# Power_Supply.net
KiCad netlist of a schematic drawn in Altium Designer
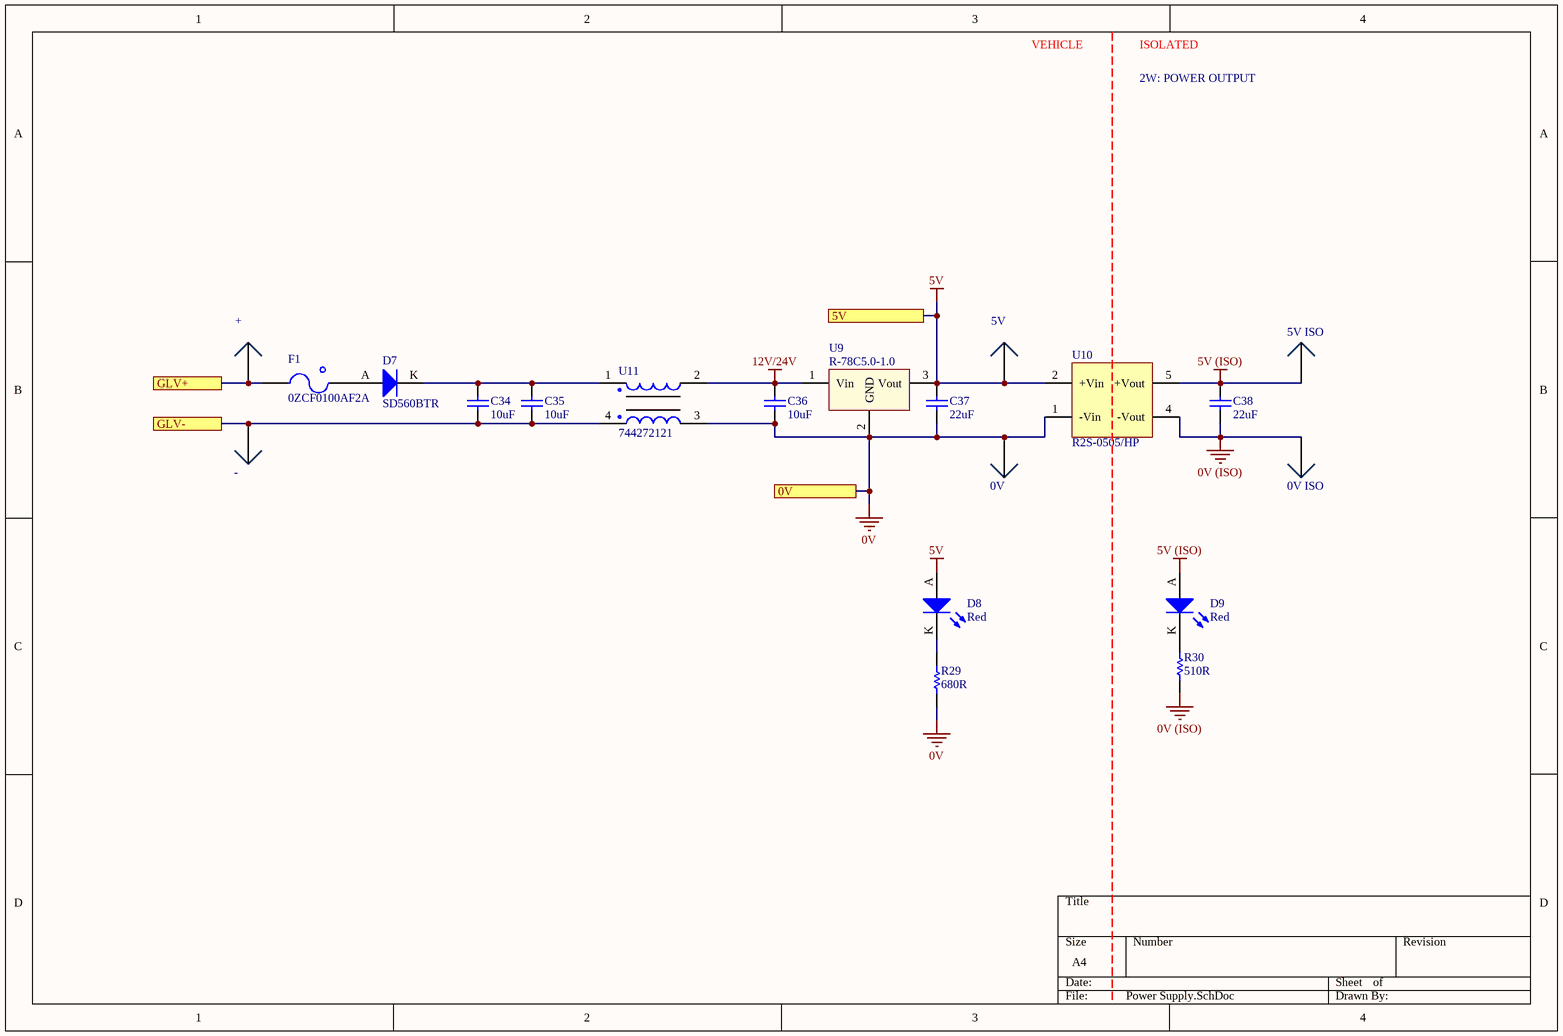
[diagram p0: Power Supply.SchDoc]

(export (version "E")
  (design (tool "Eeschema 10.0.6"))
  (components
    (comp (ref "+")
      (value "0mm")
      (footprint "SMD Test Point")
      (fields (field (name "PART NUMBER") "SMD Test Point") (field (name "CONTACT") "NA"))
      (libsource (lib "ts_20-standard-connectors") (part "Test Point"))
    )
    (comp (ref "-")
      (value "0mm")
      (footprint "SMD Test Point")
      (fields (field (name "PART NUMBER") "SMD Test Point") (field (name "CONTACT") "NA"))
      (libsource (lib "ts_20-standard-connectors") (part "Test Point"))
    )
    (comp (ref "0V")
      (value "0mm")
      (footprint "SMD Test Point")
      (fields (field (name "PART NUMBER") "SMD Test Point") (field (name "CONTACT") "NA"))
      (libsource (lib "ts_20-standard-connectors") (part "Test Point"))
    )
    (comp (ref "0V ISO")
      (value "0mm")
      (footprint "SMD Test Point")
      (fields (field (name "PART NUMBER") "SMD Test Point") (field (name "CONTACT") "NA"))
      (libsource (lib "ts_20-standard-connectors") (part "Test Point"))
    )
    (comp (ref "5V")
      (value "0mm")
      (footprint "SMD Test Point")
      (fields (field (name "PART NUMBER") "SMD Test Point") (field (name "CONTACT") "NA"))
      (libsource (lib "ts_20-standard-connectors") (part "Test Point"))
    )
    (comp (ref "5V ISO")
      (value "0mm")
      (footprint "SMD Test Point")
      (fields (field (name "PART NUMBER") "SMD Test Point") (field (name "CONTACT") "NA"))
      (libsource (lib "ts_20-standard-connectors") (part "Test Point"))
    )
    (comp (ref "C34")
      (value "10uF")
      (footprint "0805")
      (fields
        (field (name "PART NUMBER") "GRM21BR6YA106KE43L")
        (field (name "TOLERANCE") "10%")
        (field (name "MANUFACTURER") "muRata")
      )
      (libsource (lib "ts_20-standard-library") (part "Capacitor"))
    )
    (comp (ref "C35")
      (value "10uF")
      (footprint "0805")
      (fields
        (field (name "PART NUMBER") "GRM21BR6YA106KE43L")
        (field (name "TOLERANCE") "10%")
        (field (name "MANUFACTURER") "muRata")
      )
      (libsource (lib "ts_20-standard-library") (part "Capacitor"))
    )
    (comp (ref "C36")
      (value "10uF")
      (footprint "0805")
      (fields
        (field (name "PART NUMBER") "GRM21BR6YA106KE43L")
        (field (name "TOLERANCE") "10%")
        (field (name "MANUFACTURER") "muRata")
      )
      (libsource (lib "ts_20-standard-library") (part "Capacitor"))
    )
    (comp (ref "C37")
      (value "22uF")
      (footprint "1206")
      (fields
        (field (name "PART NUMBER") "CC1206MKX5R7BB226")
        (field (name "TOLERANCE") "20%")
        (field (name "MANUFACTURER") "YAGEO")
      )
      (libsource (lib "ts_20-standard-library") (part "Capacitor"))
    )
    (comp (ref "C38")
      (value "22uF")
      (footprint "1206")
      (fields
        (field (name "PART NUMBER") "CC1206MKX5R7BB226")
        (field (name "TOLERANCE") "20%")
        (field (name "MANUFACTURER") "YAGEO")
      )
      (libsource (lib "ts_20-standard-library") (part "Capacitor"))
    )
    (comp (ref "D7")
      (value "SD560BTR")
      (footprint "SMB Diode")
      (description "1.2V_F 600V 5A SMB")
      (fields
        (field (name "MANUFACTURER") "SMC Diode Solutions")
        (field (name "DIGIKEY PART NUMBER") "1655-1530-2-ND")
      )
      (libsource (lib "ts_20-standard-library") (part "Diode"))
    )
    (comp (ref "D8")
      (value "Red")
      (footprint "0805 LED")
      (description "Red LED Indication - Discrete 1.75V 0805 (2012 Metric)")
      (fields (field (name "PART NUMBER") "SML-210LTT86") (field (name "MANUFACTURER") "ROHM Semiconductor"))
      (libsource (lib "ts_20-standard-library") (part "LED"))
    )
    (comp (ref "D9")
      (value "Red")
      (footprint "0805 LED")
      (description "Red LED Indication - Discrete 1.75V 0805 (2012 Metric)")
      (fields (field (name "PART NUMBER") "SML-210LTT86") (field (name "MANUFACTURER") "ROHM Semiconductor"))
      (libsource (lib "ts_20-standard-library") (part "LED"))
    )
    (comp (ref "F1")
      (value "0ZCF0100AF2A")
      (footprint "2920")
      (description "PTC RESET FUSE 60V 1A 292")
      (fields
        (field (name "MANUFACTURER") "Littelfuse Inc.")
        (field (name "DIGIKEY PART NUMBER") "507-2070-1-ND")
      )
      (libsource (lib "ts_20-standard-library") (part "PTC Fuse"))
    )
    (comp (ref "R29")
      (value "680R")
      (footprint "0805")
      (fields
        (field (name "PART NUMBER") "RC0805FR07680RL")
        (field (name "MANUFACTURER") "YAGEO")
        (field (name "TOLERANCE") "0.01")
      )
      (libsource (lib "ts_20-standard-library") (part "Resistor"))
    )
    (comp (ref "R30")
      (value "510R")
      (footprint "0805")
      (fields
        (field (name "PART NUMBER") "RC0805FR07510RL")
        (field (name "MANUFACTURER") "YAGEO")
        (field (name "TOLERANCE") "0.01")
      )
      (libsource (lib "ts_20-standard-library") (part "Resistor"))
    )
    (comp (ref "U9")
      (value "R-78C5.0-1.0")
      (footprint "RECOM 3-SIP")
      (description "CONV DC/DC 1A 5V OUT SIP VERT")
      (fields (field (name "MANUFACTURER") "Recom") (field (name "DIGIKEY PART NUMBER") "945-1395-5-ND"))
      (libsource (lib "ts_20-standard-library") (part "R-78C5.0-1.0"))
    )
    (comp (ref "U10")
      (value "R2S-0505/HP")
      (footprint "RECOM 8-SMD (5 Pin)")
      (description "Isolated Module DC DC Converter 1 Output 3.3V 606mA 4.5V - 5.5V Input")
      (fields (field (name "MANUFACTURER") "Recom") (field (name "DIGIKEY PART NUMBER") "945-1764-5-ND"))
      (libsource (lib "ts_20-standard-library") (part "R2S-0505/HP"))
    )
    (comp (ref "U11")
      (value "744272121")
      (footprint "Wurth 4-PC Pad")
      (description "120µH @ 100kHz 2 Line Common Mode Choke Surface Mount 460 Ohms @ 30MHz 2.5A DCR 25mOhm")
      (fields
        (field (name "MANUFACTURER") "Wurth Electronics Inc")
        (field (name "DIGIKEY PART NUMBER") "732-1489-1-ND")
      )
      (libsource (lib "ts_20-standard-library") (part "744272121"))
    )
  )
  (nets
    (net (code "1") (name "/GLV+") (class "Default")
      (node (ref "+") (pin "1") (pinfunction "1_1") (pintype "passive"))
      (node (ref "F1") (pin "1") (pinfunction "1_1") (pintype "passive"))
    )
    (net (code "2") (name "/GLV-") (class "Default")
      (node (ref "-") (pin "1") (pinfunction "1_1") (pintype "passive"))
      (node (ref "C34") (pin "1") (pinfunction "1_1") (pintype "passive"))
      (node (ref "C35") (pin "1") (pinfunction "1_1") (pintype "passive"))
      (node (ref "U11") (pin "4") (pinfunction "4_4") (pintype "passive"))
    )
    (net (code "3") (name "0V") (class "Default")
      (node (ref "0V") (pin "1") (pinfunction "1_1") (pintype "passive"))
      (node (ref "C36") (pin "1") (pinfunction "1_1") (pintype "passive"))
      (node (ref "C37") (pin "1") (pinfunction "1_1") (pintype "passive"))
      (node (ref "R29") (pin "1") (pinfunction "1_1") (pintype "passive"))
      (node (ref "U10") (pin "1") (pinfunction "-Vin_1") (pintype "power_in"))
      (node (ref "U11") (pin "3") (pinfunction "3_3") (pintype "power_in"))
      (node (ref "U9") (pin "2") (pinfunction "GND_2") (pintype "passive"))
    )
    (net (code "4") (name "0V (ISO)") (class "Default")
      (node (ref "0V ISO") (pin "1") (pinfunction "1_1") (pintype "passive"))
      (node (ref "C38") (pin "1") (pinfunction "1_1") (pintype "passive"))
      (node (ref "R30") (pin "1") (pinfunction "1_1") (pintype "passive"))
      (node (ref "U10") (pin "4") (pinfunction "-Vout_4") (pintype "power_in"))
    )
    (net (code "5") (name "5V") (class "Default")
      (node (ref "5V") (pin "1") (pinfunction "1_1") (pintype "passive"))
      (node (ref "C37") (pin "2") (pinfunction "2_2") (pintype "passive"))
      (node (ref "D8") (pin "A") (pinfunction "A_A") (pintype "passive"))
      (node (ref "U10") (pin "2") (pinfunction "+Vin_2") (pintype "power_in"))
      (node (ref "U9") (pin "3") (pinfunction "Vout_3") (pintype "passive"))
    )
    (net (code "6") (name "5V (ISO)") (class "Default")
      (node (ref "5V ISO") (pin "1") (pinfunction "1_1") (pintype "passive"))
      (node (ref "C38") (pin "2") (pinfunction "2_2") (pintype "passive"))
      (node (ref "D9") (pin "A") (pinfunction "A_A") (pintype "passive"))
      (node (ref "U10") (pin "5") (pinfunction "+Vout_5") (pintype "power_in"))
    )
    (net (code "7") (name "12V{slash}24V") (class "Default")
      (node (ref "C36") (pin "2") (pinfunction "2_2") (pintype "passive"))
      (node (ref "U11") (pin "2") (pinfunction "2_2") (pintype "passive"))
      (node (ref "U9") (pin "1") (pinfunction "Vin_1") (pintype "passive"))
    )
    (net (code "8") (name "Net-(C34-Pad2)") (class "Default")
      (node (ref "C34") (pin "2") (pinfunction "2_2") (pintype "passive"))
      (node (ref "C35") (pin "2") (pinfunction "2_2") (pintype "passive"))
      (node (ref "D7") (pin "K") (pinfunction "K_K") (pintype "passive"))
      (node (ref "U11") (pin "1") (pinfunction "1_1") (pintype "passive"))
    )
    (net (code "9") (name "Net-(D7-PadA)") (class "Default")
      (node (ref "D7") (pin "A") (pinfunction "A_A") (pintype "passive"))
      (node (ref "F1") (pin "2") (pinfunction "2_2") (pintype "passive"))
    )
    (net (code "10") (name "Net-(D8-PadK)") (class "Default")
      (node (ref "D8") (pin "K") (pinfunction "K_K") (pintype "passive"))
      (node (ref "R29") (pin "2") (pinfunction "2_2") (pintype "passive"))
    )
    (net (code "11") (name "Net-(D9-PadK)") (class "Default")
      (node (ref "D9") (pin "K") (pinfunction "K_K") (pintype "passive"))
      (node (ref "R30") (pin "2") (pinfunction "2_2") (pintype "passive"))
    )
  )
)
